# SwdAdapter.net
KiCad netlist of a schematic drawn in EAGLE
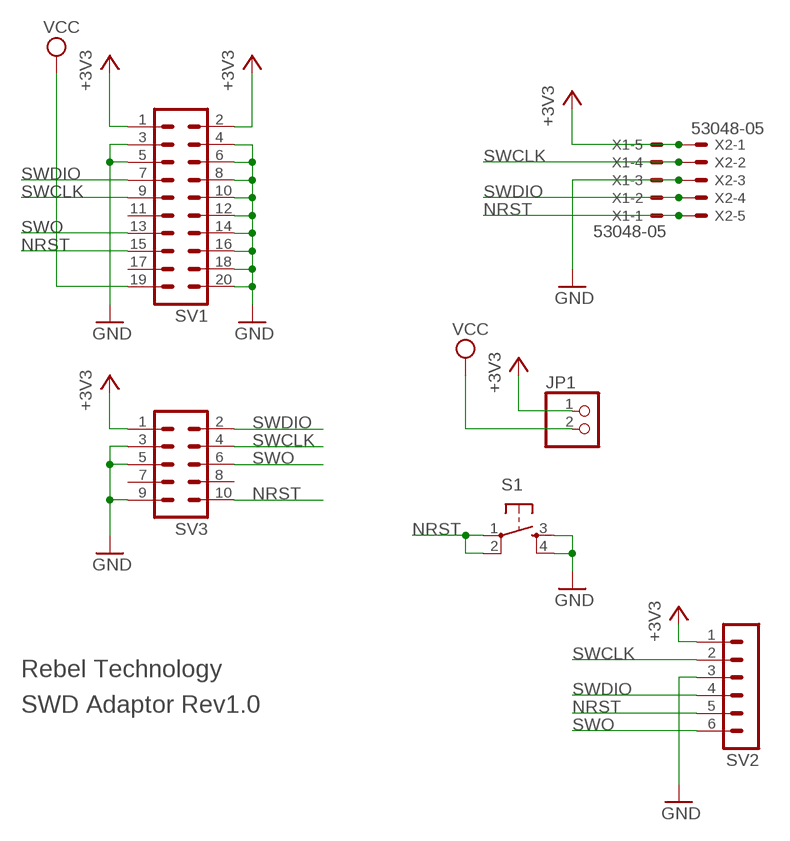
[diagram p0: schematic, sheet 1]

(export (version "E")
  (design (tool "Eeschema 10.0.6"))
  (components
    (comp (ref "JP1")
      (value "PINHD-1X2")
      (footprint "eagle-import:1X02")
      (libsource (lib "eagle-import") (part "PINHD-1X2"))
    )
    (comp (ref "S1")
      (value "TAC_SWITCHPTH")
      (footprint "eagle-import:TACTILE-PTH")
      (libsource (lib "eagle-import") (part "TAC_SWITCHPTH"))
    )
    (comp (ref "SV1")
      (value "MA10-2")
      (footprint "eagle-import:MA10-2")
      (libsource (lib "eagle-import") (part "MA10-2"))
    )
    (comp (ref "SV2")
      (value "MA06-1")
      (footprint "eagle-import:MA06-1")
      (libsource (lib "eagle-import") (part "MA06-1"))
    )
    (comp (ref "SV3")
      (value "MA05-2")
      (footprint "eagle-import:MA05-2")
      (libsource (lib "eagle-import") (part "MA05-2"))
    )
    (comp (ref "X1")
      (value "53048-05")
      (footprint "eagle-import:53048-05")
      (fields (field (name "MF") "MOLEX") (field (name "MPN") "53048-0510"))
      (libsource (lib "eagle-import") (part "53?-05048"))
    )
    (comp (ref "X2")
      (value "53048-05")
      (footprint "eagle-import:53048-05")
      (fields (field (name "MF") "MOLEX") (field (name "MPN") "53048-0510"))
      (libsource (lib "eagle-import") (part "53?-05048"))
    )
  )
  (nets
    (net (code "1") (name "+3V3") (class "Default")
      (node (ref "JP1") (pin "1") (pinfunction "1_1") (pintype "passive"))
      (node (ref "SV1") (pin "1") (pinfunction "1_1") (pintype "passive"))
      (node (ref "SV1") (pin "2") (pinfunction "2_2") (pintype "passive"))
      (node (ref "SV2") (pin "1") (pinfunction "1_1") (pintype "passive"))
      (node (ref "SV3") (pin "1") (pinfunction "1_1") (pintype "passive"))
      (node (ref "X1") (pin "5") (pinfunction "S_5") (pintype "passive"))
      (node (ref "X2") (pin "1") (pinfunction "S_1") (pintype "passive"))
    )
    (net (code "2") (name "/NRST") (class "Default")
      (node (ref "S1") (pin "1") (pinfunction "1_1") (pintype "passive"))
      (node (ref "S1") (pin "2") (pinfunction "2_2") (pintype "passive"))
      (node (ref "SV1") (pin "15") (pinfunction "15_15") (pintype "passive"))
      (node (ref "SV2") (pin "5") (pinfunction "5_5") (pintype "passive"))
      (node (ref "SV3") (pin "10") (pinfunction "10_10") (pintype "passive"))
      (node (ref "X1") (pin "1") (pinfunction "S_1") (pintype "passive"))
      (node (ref "X2") (pin "5") (pinfunction "S_5") (pintype "passive"))
    )
    (net (code "3") (name "/SWCLK") (class "Default")
      (node (ref "SV1") (pin "9") (pinfunction "9_9") (pintype "passive"))
      (node (ref "SV2") (pin "2") (pinfunction "2_2") (pintype "passive"))
      (node (ref "SV3") (pin "4") (pinfunction "4_4") (pintype "passive"))
      (node (ref "X1") (pin "4") (pinfunction "S_4") (pintype "passive"))
      (node (ref "X2") (pin "2") (pinfunction "S_2") (pintype "passive"))
    )
    (net (code "4") (name "/SWDIO") (class "Default")
      (node (ref "SV1") (pin "7") (pinfunction "7_7") (pintype "passive"))
      (node (ref "SV2") (pin "4") (pinfunction "4_4") (pintype "passive"))
      (node (ref "SV3") (pin "2") (pinfunction "2_2") (pintype "passive"))
      (node (ref "X1") (pin "2") (pinfunction "S_2") (pintype "passive"))
      (node (ref "X2") (pin "4") (pinfunction "S_4") (pintype "passive"))
    )
    (net (code "5") (name "/SWO") (class "Default")
      (node (ref "SV1") (pin "13") (pinfunction "13_13") (pintype "passive"))
      (node (ref "SV2") (pin "6") (pinfunction "6_6") (pintype "passive"))
      (node (ref "SV3") (pin "6") (pinfunction "6_6") (pintype "passive"))
    )
    (net (code "6") (name "GND") (class "Default")
      (node (ref "S1") (pin "3") (pinfunction "3_3") (pintype "passive"))
      (node (ref "S1") (pin "4") (pinfunction "4_4") (pintype "passive"))
      (node (ref "SV1") (pin "10") (pinfunction "10_10") (pintype "passive"))
      (node (ref "SV1") (pin "12") (pinfunction "12_12") (pintype "passive"))
      (node (ref "SV1") (pin "14") (pinfunction "14_14") (pintype "passive"))
      (node (ref "SV1") (pin "16") (pinfunction "16_16") (pintype "passive"))
      (node (ref "SV1") (pin "18") (pinfunction "18_18") (pintype "passive"))
      (node (ref "SV1") (pin "20") (pinfunction "20_20") (pintype "passive"))
      (node (ref "SV1") (pin "3") (pinfunction "3_3") (pintype "passive"))
      (node (ref "SV1") (pin "4") (pinfunction "4_4") (pintype "passive"))
      (node (ref "SV1") (pin "5") (pinfunction "5_5") (pintype "passive"))
      (node (ref "SV1") (pin "6") (pinfunction "6_6") (pintype "passive"))
      (node (ref "SV1") (pin "8") (pinfunction "8_8") (pintype "passive"))
      (node (ref "SV2") (pin "3") (pinfunction "3_3") (pintype "passive"))
      (node (ref "SV3") (pin "3") (pinfunction "3_3") (pintype "passive"))
      (node (ref "SV3") (pin "5") (pinfunction "5_5") (pintype "passive"))
      (node (ref "SV3") (pin "9") (pinfunction "9_9") (pintype "passive"))
      (node (ref "X1") (pin "3") (pinfunction "S_3") (pintype "passive"))
      (node (ref "X2") (pin "3") (pinfunction "S_3") (pintype "passive"))
    )
    (net (code "7") (name "VCC") (class "Default")
      (node (ref "JP1") (pin "2") (pinfunction "2_2") (pintype "passive"))
      (node (ref "SV1") (pin "19") (pinfunction "19_19") (pintype "passive"))
    )
    (net (code "8") (name "unconnected-(SV1-Pad11)") (class "Default")
      (node (ref "SV1") (pin "11") (pinfunction "11_11") (pintype "passive"))
    )
    (net (code "9") (name "unconnected-(SV1-Pad17)") (class "Default")
      (node (ref "SV1") (pin "17") (pinfunction "17_17") (pintype "passive"))
    )
    (net (code "10") (name "unconnected-(SV3-Pad7)") (class "Default")
      (node (ref "SV3") (pin "7") (pinfunction "7_7") (pintype "passive"))
    )
    (net (code "11") (name "unconnected-(SV3-Pad8)") (class "Default")
      (node (ref "SV3") (pin "8") (pinfunction "8_8") (pintype "passive"))
    )
  )
)
